# 04_Output_Display.net
KiCad netlist of a schematic drawn in Altium Designer
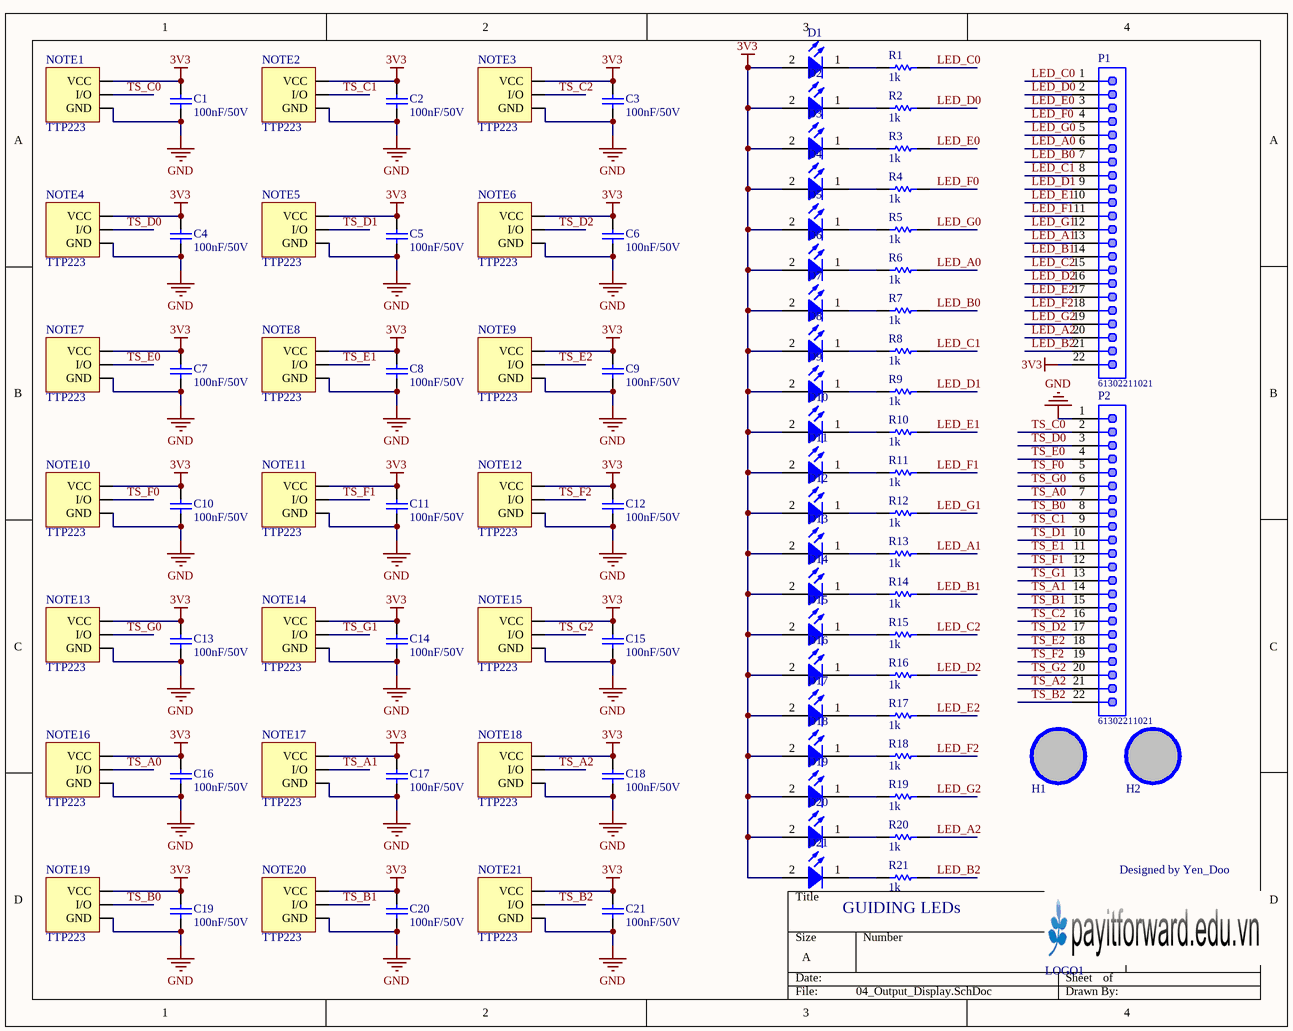
[diagram p0: 04_Output_Display.SchDoc]

(export (version "E")
  (design (tool "Eeschema 10.0.6"))
  (components
    (comp (ref "*1")
      (value "LOGO_DOO")
      (footprint "Logo_Top_Overlay")
      (libsource (lib "YenDoo") (part "LOGO_DOO"))
    )
    (comp (ref "C1")
      (value "100nF/50V")
      (footprint "CAP-SM-0805")
      (description "CAP CER 0.1UF 50V Y5V 0805")
      (fields
        (field (name "MANUFACTURER") "Samsung Electro-Mechanics")
        (field (name "MANUFACTURER PART NUMBER") "CL21F104ZBCNNNC")
      )
      (libsource (lib "Capacitor") (part "Cap-100nF-50V-0805"))
    )
    (comp (ref "C2")
      (value "100nF/50V")
      (footprint "CAP-SM-0805")
      (description "CAP CER 0.1UF 50V Y5V 0805")
      (fields
        (field (name "MANUFACTURER") "Samsung Electro-Mechanics")
        (field (name "MANUFACTURER PART NUMBER") "CL21F104ZBCNNNC")
      )
      (libsource (lib "Capacitor") (part "Cap-100nF-50V-0805"))
    )
    (comp (ref "C3")
      (value "100nF/50V")
      (footprint "CAP-SM-0805")
      (description "CAP CER 0.1UF 50V Y5V 0805")
      (fields
        (field (name "MANUFACTURER") "Samsung Electro-Mechanics")
        (field (name "MANUFACTURER PART NUMBER") "CL21F104ZBCNNNC")
      )
      (libsource (lib "Capacitor") (part "Cap-100nF-50V-0805"))
    )
    (comp (ref "C4")
      (value "100nF/50V")
      (footprint "CAP-SM-0805")
      (description "CAP CER 0.1UF 50V Y5V 0805")
      (fields
        (field (name "MANUFACTURER") "Samsung Electro-Mechanics")
        (field (name "MANUFACTURER PART NUMBER") "CL21F104ZBCNNNC")
      )
      (libsource (lib "Capacitor") (part "Cap-100nF-50V-0805"))
    )
    (comp (ref "C5")
      (value "100nF/50V")
      (footprint "CAP-SM-0805")
      (description "CAP CER 0.1UF 50V Y5V 0805")
      (fields
        (field (name "MANUFACTURER") "Samsung Electro-Mechanics")
        (field (name "MANUFACTURER PART NUMBER") "CL21F104ZBCNNNC")
      )
      (libsource (lib "Capacitor") (part "Cap-100nF-50V-0805"))
    )
    (comp (ref "C6")
      (value "100nF/50V")
      (footprint "CAP-SM-0805")
      (description "CAP CER 0.1UF 50V Y5V 0805")
      (fields
        (field (name "MANUFACTURER") "Samsung Electro-Mechanics")
        (field (name "MANUFACTURER PART NUMBER") "CL21F104ZBCNNNC")
      )
      (libsource (lib "Capacitor") (part "Cap-100nF-50V-0805"))
    )
    (comp (ref "C7")
      (value "100nF/50V")
      (footprint "CAP-SM-0805")
      (description "CAP CER 0.1UF 50V Y5V 0805")
      (fields
        (field (name "MANUFACTURER") "Samsung Electro-Mechanics")
        (field (name "MANUFACTURER PART NUMBER") "CL21F104ZBCNNNC")
      )
      (libsource (lib "Capacitor") (part "Cap-100nF-50V-0805"))
    )
    (comp (ref "C8")
      (value "100nF/50V")
      (footprint "CAP-SM-0805")
      (description "CAP CER 0.1UF 50V Y5V 0805")
      (fields
        (field (name "MANUFACTURER") "Samsung Electro-Mechanics")
        (field (name "MANUFACTURER PART NUMBER") "CL21F104ZBCNNNC")
      )
      (libsource (lib "Capacitor") (part "Cap-100nF-50V-0805"))
    )
    (comp (ref "C9")
      (value "100nF/50V")
      (footprint "CAP-SM-0805")
      (description "CAP CER 0.1UF 50V Y5V 0805")
      (fields
        (field (name "MANUFACTURER") "Samsung Electro-Mechanics")
        (field (name "MANUFACTURER PART NUMBER") "CL21F104ZBCNNNC")
      )
      (libsource (lib "Capacitor") (part "Cap-100nF-50V-0805"))
    )
    (comp (ref "C10")
      (value "100nF/50V")
      (footprint "CAP-SM-0805")
      (description "CAP CER 0.1UF 50V Y5V 0805")
      (fields
        (field (name "MANUFACTURER") "Samsung Electro-Mechanics")
        (field (name "MANUFACTURER PART NUMBER") "CL21F104ZBCNNNC")
      )
      (libsource (lib "Capacitor") (part "Cap-100nF-50V-0805"))
    )
    (comp (ref "C11")
      (value "100nF/50V")
      (footprint "CAP-SM-0805")
      (description "CAP CER 0.1UF 50V Y5V 0805")
      (fields
        (field (name "MANUFACTURER") "Samsung Electro-Mechanics")
        (field (name "MANUFACTURER PART NUMBER") "CL21F104ZBCNNNC")
      )
      (libsource (lib "Capacitor") (part "Cap-100nF-50V-0805"))
    )
    (comp (ref "C12")
      (value "100nF/50V")
      (footprint "CAP-SM-0805")
      (description "CAP CER 0.1UF 50V Y5V 0805")
      (fields
        (field (name "MANUFACTURER") "Samsung Electro-Mechanics")
        (field (name "MANUFACTURER PART NUMBER") "CL21F104ZBCNNNC")
      )
      (libsource (lib "Capacitor") (part "Cap-100nF-50V-0805"))
    )
    (comp (ref "C13")
      (value "100nF/50V")
      (footprint "CAP-SM-0805")
      (description "CAP CER 0.1UF 50V Y5V 0805")
      (fields
        (field (name "MANUFACTURER") "Samsung Electro-Mechanics")
        (field (name "MANUFACTURER PART NUMBER") "CL21F104ZBCNNNC")
      )
      (libsource (lib "Capacitor") (part "Cap-100nF-50V-0805"))
    )
    (comp (ref "C14")
      (value "100nF/50V")
      (footprint "CAP-SM-0805")
      (description "CAP CER 0.1UF 50V Y5V 0805")
      (fields
        (field (name "MANUFACTURER") "Samsung Electro-Mechanics")
        (field (name "MANUFACTURER PART NUMBER") "CL21F104ZBCNNNC")
      )
      (libsource (lib "Capacitor") (part "Cap-100nF-50V-0805"))
    )
    (comp (ref "C15")
      (value "100nF/50V")
      (footprint "CAP-SM-0805")
      (description "CAP CER 0.1UF 50V Y5V 0805")
      (fields
        (field (name "MANUFACTURER") "Samsung Electro-Mechanics")
        (field (name "MANUFACTURER PART NUMBER") "CL21F104ZBCNNNC")
      )
      (libsource (lib "Capacitor") (part "Cap-100nF-50V-0805"))
    )
    (comp (ref "C16")
      (value "100nF/50V")
      (footprint "CAP-SM-0805")
      (description "CAP CER 0.1UF 50V Y5V 0805")
      (fields
        (field (name "MANUFACTURER") "Samsung Electro-Mechanics")
        (field (name "MANUFACTURER PART NUMBER") "CL21F104ZBCNNNC")
      )
      (libsource (lib "Capacitor") (part "Cap-100nF-50V-0805"))
    )
    (comp (ref "C17")
      (value "100nF/50V")
      (footprint "CAP-SM-0805")
      (description "CAP CER 0.1UF 50V Y5V 0805")
      (fields
        (field (name "MANUFACTURER") "Samsung Electro-Mechanics")
        (field (name "MANUFACTURER PART NUMBER") "CL21F104ZBCNNNC")
      )
      (libsource (lib "Capacitor") (part "Cap-100nF-50V-0805"))
    )
    (comp (ref "C18")
      (value "100nF/50V")
      (footprint "CAP-SM-0805")
      (description "CAP CER 0.1UF 50V Y5V 0805")
      (fields
        (field (name "MANUFACTURER") "Samsung Electro-Mechanics")
        (field (name "MANUFACTURER PART NUMBER") "CL21F104ZBCNNNC")
      )
      (libsource (lib "Capacitor") (part "Cap-100nF-50V-0805"))
    )
    (comp (ref "C19")
      (value "100nF/50V")
      (footprint "CAP-SM-0805")
      (description "CAP CER 0.1UF 50V Y5V 0805")
      (fields
        (field (name "MANUFACTURER") "Samsung Electro-Mechanics")
        (field (name "MANUFACTURER PART NUMBER") "CL21F104ZBCNNNC")
      )
      (libsource (lib "Capacitor") (part "Cap-100nF-50V-0805"))
    )
    (comp (ref "C20")
      (value "100nF/50V")
      (footprint "CAP-SM-0805")
      (description "CAP CER 0.1UF 50V Y5V 0805")
      (fields
        (field (name "MANUFACTURER") "Samsung Electro-Mechanics")
        (field (name "MANUFACTURER PART NUMBER") "CL21F104ZBCNNNC")
      )
      (libsource (lib "Capacitor") (part "Cap-100nF-50V-0805"))
    )
    (comp (ref "C21")
      (value "100nF/50V")
      (footprint "CAP-SM-0805")
      (description "CAP CER 0.1UF 50V Y5V 0805")
      (fields
        (field (name "MANUFACTURER") "Samsung Electro-Mechanics")
        (field (name "MANUFACTURER PART NUMBER") "CL21F104ZBCNNNC")
      )
      (libsource (lib "Capacitor") (part "Cap-100nF-50V-0805"))
    )
    (comp (ref "D1")
      (value "Blue, 3.2V")
      (footprint "WL-SMCW_0805")
      (description "WL-SMCW SMT Mono-color Chip LED Waterclear, size 0805, Blue, 3.2V, 140deg")
      (fields (field (name "PART NUMBER") "150080BS75000") (field (name "PUBLISHER") "Wurth Elektronik"))
      (libsource (lib "Altium_WL-SMCW (rev20a)") (part "150080BS75000"))
    )
    (comp (ref "D2")
      (value "Blue, 3.2V")
      (footprint "WL-SMCW_0805")
      (description "WL-SMCW SMT Mono-color Chip LED Waterclear, size 0805, Blue, 3.2V, 140deg")
      (fields (field (name "PART NUMBER") "150080BS75000") (field (name "PUBLISHER") "Wurth Elektronik"))
      (libsource (lib "Altium_WL-SMCW (rev20a)") (part "150080BS75000"))
    )
    (comp (ref "D3")
      (value "Blue, 3.2V")
      (footprint "WL-SMCW_0805")
      (description "WL-SMCW SMT Mono-color Chip LED Waterclear, size 0805, Blue, 3.2V, 140deg")
      (fields (field (name "PART NUMBER") "150080BS75000") (field (name "PUBLISHER") "Wurth Elektronik"))
      (libsource (lib "Altium_WL-SMCW (rev20a)") (part "150080BS75000"))
    )
    (comp (ref "D4")
      (value "Blue, 3.2V")
      (footprint "WL-SMCW_0805")
      (description "WL-SMCW SMT Mono-color Chip LED Waterclear, size 0805, Blue, 3.2V, 140deg")
      (fields (field (name "PART NUMBER") "150080BS75000") (field (name "PUBLISHER") "Wurth Elektronik"))
      (libsource (lib "Altium_WL-SMCW (rev20a)") (part "150080BS75000"))
    )
    (comp (ref "D5")
      (value "Blue, 3.2V")
      (footprint "WL-SMCW_0805")
      (description "WL-SMCW SMT Mono-color Chip LED Waterclear, size 0805, Blue, 3.2V, 140deg")
      (fields (field (name "PART NUMBER") "150080BS75000") (field (name "PUBLISHER") "Wurth Elektronik"))
      (libsource (lib "Altium_WL-SMCW (rev20a)") (part "150080BS75000"))
    )
    (comp (ref "D6")
      (value "Blue, 3.2V")
      (footprint "WL-SMCW_0805")
      (description "WL-SMCW SMT Mono-color Chip LED Waterclear, size 0805, Blue, 3.2V, 140deg")
      (fields (field (name "PART NUMBER") "150080BS75000") (field (name "PUBLISHER") "Wurth Elektronik"))
      (libsource (lib "Altium_WL-SMCW (rev20a)") (part "150080BS75000"))
    )
    (comp (ref "D7")
      (value "Blue, 3.2V")
      (footprint "WL-SMCW_0805")
      (description "WL-SMCW SMT Mono-color Chip LED Waterclear, size 0805, Blue, 3.2V, 140deg")
      (fields (field (name "PART NUMBER") "150080BS75000") (field (name "PUBLISHER") "Wurth Elektronik"))
      (libsource (lib "Altium_WL-SMCW (rev20a)") (part "150080BS75000"))
    )
    (comp (ref "D8")
      (value "Blue, 3.2V")
      (footprint "WL-SMCW_0805")
      (description "WL-SMCW SMT Mono-color Chip LED Waterclear, size 0805, Blue, 3.2V, 140deg")
      (fields (field (name "PART NUMBER") "150080BS75000") (field (name "PUBLISHER") "Wurth Elektronik"))
      (libsource (lib "Altium_WL-SMCW (rev20a)") (part "150080BS75000"))
    )
    (comp (ref "D9")
      (value "Blue, 3.2V")
      (footprint "WL-SMCW_0805")
      (description "WL-SMCW SMT Mono-color Chip LED Waterclear, size 0805, Blue, 3.2V, 140deg")
      (fields (field (name "PART NUMBER") "150080BS75000") (field (name "PUBLISHER") "Wurth Elektronik"))
      (libsource (lib "Altium_WL-SMCW (rev20a)") (part "150080BS75000"))
    )
    (comp (ref "D10")
      (value "Blue, 3.2V")
      (footprint "WL-SMCW_0805")
      (description "WL-SMCW SMT Mono-color Chip LED Waterclear, size 0805, Blue, 3.2V, 140deg")
      (fields (field (name "PART NUMBER") "150080BS75000") (field (name "PUBLISHER") "Wurth Elektronik"))
      (libsource (lib "Altium_WL-SMCW (rev20a)") (part "150080BS75000"))
    )
    (comp (ref "D11")
      (value "Blue, 3.2V")
      (footprint "WL-SMCW_0805")
      (description "WL-SMCW SMT Mono-color Chip LED Waterclear, size 0805, Blue, 3.2V, 140deg")
      (fields (field (name "PART NUMBER") "150080BS75000") (field (name "PUBLISHER") "Wurth Elektronik"))
      (libsource (lib "Altium_WL-SMCW (rev20a)") (part "150080BS75000"))
    )
    (comp (ref "D12")
      (value "Blue, 3.2V")
      (footprint "WL-SMCW_0805")
      (description "WL-SMCW SMT Mono-color Chip LED Waterclear, size 0805, Blue, 3.2V, 140deg")
      (fields (field (name "PART NUMBER") "150080BS75000") (field (name "PUBLISHER") "Wurth Elektronik"))
      (libsource (lib "Altium_WL-SMCW (rev20a)") (part "150080BS75000"))
    )
    (comp (ref "D13")
      (value "Blue, 3.2V")
      (footprint "WL-SMCW_0805")
      (description "WL-SMCW SMT Mono-color Chip LED Waterclear, size 0805, Blue, 3.2V, 140deg")
      (fields (field (name "PART NUMBER") "150080BS75000") (field (name "PUBLISHER") "Wurth Elektronik"))
      (libsource (lib "Altium_WL-SMCW (rev20a)") (part "150080BS75000"))
    )
    (comp (ref "D14")
      (value "Blue, 3.2V")
      (footprint "WL-SMCW_0805")
      (description "WL-SMCW SMT Mono-color Chip LED Waterclear, size 0805, Blue, 3.2V, 140deg")
      (fields (field (name "PART NUMBER") "150080BS75000") (field (name "PUBLISHER") "Wurth Elektronik"))
      (libsource (lib "Altium_WL-SMCW (rev20a)") (part "150080BS75000"))
    )
    (comp (ref "D15")
      (value "Blue, 3.2V")
      (footprint "WL-SMCW_0805")
      (description "WL-SMCW SMT Mono-color Chip LED Waterclear, size 0805, Blue, 3.2V, 140deg")
      (fields (field (name "PART NUMBER") "150080BS75000") (field (name "PUBLISHER") "Wurth Elektronik"))
      (libsource (lib "Altium_WL-SMCW (rev20a)") (part "150080BS75000"))
    )
    (comp (ref "D16")
      (value "Blue, 3.2V")
      (footprint "WL-SMCW_0805")
      (description "WL-SMCW SMT Mono-color Chip LED Waterclear, size 0805, Blue, 3.2V, 140deg")
      (fields (field (name "PART NUMBER") "150080BS75000") (field (name "PUBLISHER") "Wurth Elektronik"))
      (libsource (lib "Altium_WL-SMCW (rev20a)") (part "150080BS75000"))
    )
    (comp (ref "D17")
      (value "Blue, 3.2V")
      (footprint "WL-SMCW_0805")
      (description "WL-SMCW SMT Mono-color Chip LED Waterclear, size 0805, Blue, 3.2V, 140deg")
      (fields (field (name "PART NUMBER") "150080BS75000") (field (name "PUBLISHER") "Wurth Elektronik"))
      (libsource (lib "Altium_WL-SMCW (rev20a)") (part "150080BS75000"))
    )
    (comp (ref "D18")
      (value "Blue, 3.2V")
      (footprint "WL-SMCW_0805")
      (description "WL-SMCW SMT Mono-color Chip LED Waterclear, size 0805, Blue, 3.2V, 140deg")
      (fields (field (name "PART NUMBER") "150080BS75000") (field (name "PUBLISHER") "Wurth Elektronik"))
      (libsource (lib "Altium_WL-SMCW (rev20a)") (part "150080BS75000"))
    )
    (comp (ref "D19")
      (value "Blue, 3.2V")
      (footprint "WL-SMCW_0805")
      (description "WL-SMCW SMT Mono-color Chip LED Waterclear, size 0805, Blue, 3.2V, 140deg")
      (fields (field (name "PART NUMBER") "150080BS75000") (field (name "PUBLISHER") "Wurth Elektronik"))
      (libsource (lib "Altium_WL-SMCW (rev20a)") (part "150080BS75000"))
    )
    (comp (ref "D20")
      (value "Blue, 3.2V")
      (footprint "WL-SMCW_0805")
      (description "WL-SMCW SMT Mono-color Chip LED Waterclear, size 0805, Blue, 3.2V, 140deg")
      (fields (field (name "PART NUMBER") "150080BS75000") (field (name "PUBLISHER") "Wurth Elektronik"))
      (libsource (lib "Altium_WL-SMCW (rev20a)") (part "150080BS75000"))
    )
    (comp (ref "D21")
      (value "Blue, 3.2V")
      (footprint "WL-SMCW_0805")
      (description "WL-SMCW SMT Mono-color Chip LED Waterclear, size 0805, Blue, 3.2V, 140deg")
      (fields (field (name "PART NUMBER") "150080BS75000") (field (name "PUBLISHER") "Wurth Elektronik"))
      (libsource (lib "Altium_WL-SMCW (rev20a)") (part "150080BS75000"))
    )
    (comp (ref "H1")
      (value "Hole")
      (footprint "LO KHOAN 3MM")
      (description "Hole 3mm")
      (libsource (lib "PIF_Library") (part "Hole"))
    )
    (comp (ref "H2")
      (value "Hole")
      (footprint "LO KHOAN 3MM")
      (description "Hole 3mm")
      (libsource (lib "PIF_Library") (part "Hole"))
    )
    (comp (ref "LOGO1")
      (value "LOGO PIF")
      (footprint "PIF LOGO BIG SSTOP")
      (libsource (lib "PIF_Library") (part "LOGO PIF"))
    )
    (comp (ref "NOTE1") (value "TTP223") (footprint "TTP223") (libsource (lib "YenDoo") (part "TTP223")))
    (comp (ref "NOTE2") (value "TTP223") (footprint "TTP223") (libsource (lib "YenDoo") (part "TTP223")))
    (comp (ref "NOTE3") (value "TTP223") (footprint "TTP223") (libsource (lib "YenDoo") (part "TTP223")))
    (comp (ref "NOTE4") (value "TTP223") (footprint "TTP223") (libsource (lib "YenDoo") (part "TTP223")))
    (comp (ref "NOTE5") (value "TTP223") (footprint "TTP223") (libsource (lib "YenDoo") (part "TTP223")))
    (comp (ref "NOTE6") (value "TTP223") (footprint "TTP223") (libsource (lib "YenDoo") (part "TTP223")))
    (comp (ref "NOTE7") (value "TTP223") (footprint "TTP223") (libsource (lib "YenDoo") (part "TTP223")))
    (comp (ref "NOTE8") (value "TTP223") (footprint "TTP223") (libsource (lib "YenDoo") (part "TTP223")))
    (comp (ref "NOTE9") (value "TTP223") (footprint "TTP223") (libsource (lib "YenDoo") (part "TTP223")))
    (comp (ref "NOTE10") (value "TTP223") (footprint "TTP223") (libsource (lib "YenDoo") (part "TTP223")))
    (comp (ref "NOTE11") (value "TTP223") (footprint "TTP223") (libsource (lib "YenDoo") (part "TTP223")))
    (comp (ref "NOTE12") (value "TTP223") (footprint "TTP223") (libsource (lib "YenDoo") (part "TTP223")))
    (comp (ref "NOTE13") (value "TTP223") (footprint "TTP223") (libsource (lib "YenDoo") (part "TTP223")))
    (comp (ref "NOTE14") (value "TTP223") (footprint "TTP223") (libsource (lib "YenDoo") (part "TTP223")))
    (comp (ref "NOTE15") (value "TTP223") (footprint "TTP223") (libsource (lib "YenDoo") (part "TTP223")))
    (comp (ref "NOTE16") (value "TTP223") (footprint "TTP223") (libsource (lib "YenDoo") (part "TTP223")))
    (comp (ref "NOTE17") (value "TTP223") (footprint "TTP223") (libsource (lib "YenDoo") (part "TTP223")))
    (comp (ref "NOTE18") (value "TTP223") (footprint "TTP223") (libsource (lib "YenDoo") (part "TTP223")))
    (comp (ref "NOTE19") (value "TTP223") (footprint "TTP223") (libsource (lib "YenDoo") (part "TTP223")))
    (comp (ref "NOTE20") (value "TTP223") (footprint "TTP223") (libsource (lib "YenDoo") (part "TTP223")))
    (comp (ref "NOTE21") (value "TTP223") (footprint "TTP223") (libsource (lib "YenDoo") (part "TTP223")))
    (comp (ref "P1")
      (value "61302211021")
      (footprint "61302211021")
      (description "WR-PHD Pin Header, THT, pitch 2.54mm, Single Row, Angled, 22p")
      (fields (field (name "MANUFACTURER") "Wurth Elektronik"))
      (libsource (lib "Altium_WR-PHD (rev20a)") (part "61302211021"))
    )
    (comp (ref "P2")
      (value "61302211021")
      (footprint "61302211021")
      (description "WR-PHD Pin Header, THT, pitch 2.54mm, Single Row, Angled, 22p")
      (fields (field (name "MANUFACTURER") "Wurth Elektronik"))
      (libsource (lib "Altium_WR-PHD (rev20a)") (part "61302211021"))
    )
    (comp (ref "R1")
      (value "1k")
      (footprint "RES-SM-0805")
      (description "Resistor")
      (fields (field (name "Comment") "RESISTOR SMD"))
      (libsource (lib "PIF_Library") (part "RESISTOR SMD"))
    )
    (comp (ref "R2")
      (value "1k")
      (footprint "RES-SM-0805")
      (description "Resistor")
      (fields (field (name "Comment") "RESISTOR SMD"))
      (libsource (lib "PIF_Library") (part "RESISTOR SMD"))
    )
    (comp (ref "R3")
      (value "1k")
      (footprint "RES-SM-0805")
      (description "Resistor")
      (fields (field (name "Comment") "RESISTOR SMD"))
      (libsource (lib "PIF_Library") (part "RESISTOR SMD"))
    )
    (comp (ref "R4")
      (value "1k")
      (footprint "RES-SM-0805")
      (description "Resistor")
      (fields (field (name "Comment") "RESISTOR SMD"))
      (libsource (lib "PIF_Library") (part "RESISTOR SMD"))
    )
    (comp (ref "R5")
      (value "1k")
      (footprint "RES-SM-0805")
      (description "Resistor")
      (fields (field (name "Comment") "RESISTOR SMD"))
      (libsource (lib "PIF_Library") (part "RESISTOR SMD"))
    )
    (comp (ref "R6")
      (value "1k")
      (footprint "RES-SM-0805")
      (description "Resistor")
      (fields (field (name "Comment") "RESISTOR SMD"))
      (libsource (lib "PIF_Library") (part "RESISTOR SMD"))
    )
    (comp (ref "R7")
      (value "1k")
      (footprint "RES-SM-0805")
      (description "Resistor")
      (fields (field (name "Comment") "RESISTOR SMD"))
      (libsource (lib "PIF_Library") (part "RESISTOR SMD"))
    )
    (comp (ref "R8")
      (value "1k")
      (footprint "RES-SM-0805")
      (description "Resistor")
      (fields (field (name "Comment") "RESISTOR SMD"))
      (libsource (lib "PIF_Library") (part "RESISTOR SMD"))
    )
    (comp (ref "R9")
      (value "1k")
      (footprint "RES-SM-0805")
      (description "Resistor")
      (fields (field (name "Comment") "RESISTOR SMD"))
      (libsource (lib "PIF_Library") (part "RESISTOR SMD"))
    )
    (comp (ref "R10")
      (value "1k")
      (footprint "RES-SM-0805")
      (description "Resistor")
      (fields (field (name "Comment") "RESISTOR SMD"))
      (libsource (lib "PIF_Library") (part "RESISTOR SMD"))
    )
    (comp (ref "R11")
      (value "1k")
      (footprint "RES-SM-0805")
      (description "Resistor")
      (fields (field (name "Comment") "RESISTOR SMD"))
      (libsource (lib "PIF_Library") (part "RESISTOR SMD"))
    )
    (comp (ref "R12")
      (value "1k")
      (footprint "RES-SM-0805")
      (description "Resistor")
      (fields (field (name "Comment") "RESISTOR SMD"))
      (libsource (lib "PIF_Library") (part "RESISTOR SMD"))
    )
    (comp (ref "R13")
      (value "1k")
      (footprint "RES-SM-0805")
      (description "Resistor")
      (fields (field (name "Comment") "RESISTOR SMD"))
      (libsource (lib "PIF_Library") (part "RESISTOR SMD"))
    )
    (comp (ref "R14")
      (value "1k")
      (footprint "RES-SM-0805")
      (description "Resistor")
      (fields (field (name "Comment") "RESISTOR SMD"))
      (libsource (lib "PIF_Library") (part "RESISTOR SMD"))
    )
    (comp (ref "R15")
      (value "1k")
      (footprint "RES-SM-0805")
      (description "Resistor")
      (fields (field (name "Comment") "RESISTOR SMD"))
      (libsource (lib "PIF_Library") (part "RESISTOR SMD"))
    )
    (comp (ref "R16")
      (value "1k")
      (footprint "RES-SM-0805")
      (description "Resistor")
      (fields (field (name "Comment") "RESISTOR SMD"))
      (libsource (lib "PIF_Library") (part "RESISTOR SMD"))
    )
    (comp (ref "R17")
      (value "1k")
      (footprint "RES-SM-0805")
      (description "Resistor")
      (fields (field (name "Comment") "RESISTOR SMD"))
      (libsource (lib "PIF_Library") (part "RESISTOR SMD"))
    )
    (comp (ref "R18")
      (value "1k")
      (footprint "RES-SM-0805")
      (description "Resistor")
      (fields (field (name "Comment") "RESISTOR SMD"))
      (libsource (lib "PIF_Library") (part "RESISTOR SMD"))
    )
    (comp (ref "R19")
      (value "1k")
      (footprint "RES-SM-0805")
      (description "Resistor")
      (fields (field (name "Comment") "RESISTOR SMD"))
      (libsource (lib "PIF_Library") (part "RESISTOR SMD"))
    )
    (comp (ref "R20")
      (value "1k")
      (footprint "RES-SM-0805")
      (description "Resistor")
      (fields (field (name "Comment") "RESISTOR SMD"))
      (libsource (lib "PIF_Library") (part "RESISTOR SMD"))
    )
    (comp (ref "R21")
      (value "1k")
      (footprint "RES-SM-0805")
      (description "Resistor")
      (fields (field (name "Comment") "RESISTOR SMD"))
      (libsource (lib "PIF_Library") (part "RESISTOR SMD"))
    )
  )
  (nets
    (net (code "1") (name "/LED_A0") (class "Default")
      (node (ref "P1") (pin "6") (pinfunction "6_6") (pintype "passive"))
      (node (ref "R6") (pin "1") (pinfunction "1_1") (pintype "passive"))
    )
    (net (code "2") (name "/LED_A1") (class "Default")
      (node (ref "P1") (pin "13") (pinfunction "13_13") (pintype "passive"))
      (node (ref "R13") (pin "1") (pinfunction "1_1") (pintype "passive"))
    )
    (net (code "3") (name "/LED_A2") (class "Default")
      (node (ref "P1") (pin "20") (pinfunction "20_20") (pintype "passive"))
      (node (ref "R20") (pin "1") (pinfunction "1_1") (pintype "passive"))
    )
    (net (code "4") (name "/LED_B0") (class "Default")
      (node (ref "P1") (pin "7") (pinfunction "7_7") (pintype "passive"))
      (node (ref "R7") (pin "1") (pinfunction "1_1") (pintype "passive"))
    )
    (net (code "5") (name "/LED_B1") (class "Default")
      (node (ref "P1") (pin "14") (pinfunction "14_14") (pintype "passive"))
      (node (ref "R14") (pin "1") (pinfunction "1_1") (pintype "passive"))
    )
    (net (code "6") (name "/LED_B2") (class "Default")
      (node (ref "P1") (pin "21") (pinfunction "21_21") (pintype "passive"))
      (node (ref "R21") (pin "1") (pinfunction "1_1") (pintype "passive"))
    )
    (net (code "7") (name "/LED_C0") (class "Default")
      (node (ref "P1") (pin "1") (pinfunction "1_1") (pintype "passive"))
      (node (ref "R1") (pin "1") (pinfunction "1_1") (pintype "passive"))
    )
    (net (code "8") (name "/LED_C1") (class "Default")
      (node (ref "P1") (pin "8") (pinfunction "8_8") (pintype "passive"))
      (node (ref "R8") (pin "1") (pinfunction "1_1") (pintype "passive"))
    )
    (net (code "9") (name "/LED_C2") (class "Default")
      (node (ref "P1") (pin "15") (pinfunction "15_15") (pintype "passive"))
      (node (ref "R15") (pin "1") (pinfunction "1_1") (pintype "passive"))
    )
    (net (code "10") (name "/LED_D0") (class "Default")
      (node (ref "P1") (pin "2") (pinfunction "2_2") (pintype "passive"))
      (node (ref "R2") (pin "1") (pinfunction "1_1") (pintype "passive"))
    )
    (net (code "11") (name "/LED_D1") (class "Default")
      (node (ref "P1") (pin "9") (pinfunction "9_9") (pintype "passive"))
      (node (ref "R9") (pin "1") (pinfunction "1_1") (pintype "passive"))
    )
    (net (code "12") (name "/LED_D2") (class "Default")
      (node (ref "P1") (pin "16") (pinfunction "16_16") (pintype "passive"))
      (node (ref "R16") (pin "1") (pinfunction "1_1") (pintype "passive"))
    )
    (net (code "13") (name "/LED_E0") (class "Default")
      (node (ref "P1") (pin "3") (pinfunction "3_3") (pintype "passive"))
      (node (ref "R3") (pin "1") (pinfunction "1_1") (pintype "passive"))
    )
    (net (code "14") (name "/LED_E1") (class "Default")
      (node (ref "P1") (pin "10") (pinfunction "10_10") (pintype "passive"))
      (node (ref "R10") (pin "1") (pinfunction "1_1") (pintype "passive"))
    )
    (net (code "15") (name "/LED_E2") (class "Default")
      (node (ref "P1") (pin "17") (pinfunction "17_17") (pintype "passive"))
      (node (ref "R17") (pin "1") (pinfunction "1_1") (pintype "passive"))
    )
    (net (code "16") (name "/LED_F0") (class "Default")
      (node (ref "P1") (pin "4") (pinfunction "4_4") (pintype "passive"))
      (node (ref "R4") (pin "1") (pinfunction "1_1") (pintype "passive"))
    )
    (net (code "17") (name "/LED_F1") (class "Default")
      (node (ref "P1") (pin "11") (pinfunction "11_11") (pintype "passive"))
      (node (ref "R11") (pin "1") (pinfunction "1_1") (pintype "passive"))
    )
    (net (code "18") (name "/LED_F2") (class "Default")
      (node (ref "P1") (pin "18") (pinfunction "18_18") (pintype "passive"))
      (node (ref "R18") (pin "1") (pinfunction "1_1") (pintype "passive"))
    )
    (net (code "19") (name "/LED_G0") (class "Default")
      (node (ref "P1") (pin "5") (pinfunction "5_5") (pintype "passive"))
      (node (ref "R5") (pin "1") (pinfunction "1_1") (pintype "passive"))
    )
    (net (code "20") (name "/LED_G1") (class "Default")
      (node (ref "P1") (pin "12") (pinfunction "12_12") (pintype "passive"))
      (node (ref "R12") (pin "1") (pinfunction "1_1") (pintype "passive"))
    )
    (net (code "21") (name "/LED_G2") (class "Default")
      (node (ref "P1") (pin "19") (pinfunction "19_19") (pintype "passive"))
      (node (ref "R19") (pin "1") (pinfunction "1_1") (pintype "passive"))
    )
    (net (code "22") (name "/TS_A0") (class "Default")
      (node (ref "NOTE16") (pin "2") (pinfunction "I/O_2") (pintype "passive"))
      (node (ref "P2") (pin "7") (pinfunction "7_7") (pintype "passive"))
    )
    (net (code "23") (name "/TS_A1") (class "Default")
      (node (ref "NOTE17") (pin "2") (pinfunction "I/O_2") (pintype "passive"))
      (node (ref "P2") (pin "14") (pinfunction "14_14") (pintype "passive"))
    )
    (net (code "24") (name "/TS_A2") (class "Default")
      (node (ref "NOTE18") (pin "2") (pinfunction "I/O_2") (pintype "passive"))
      (node (ref "P2") (pin "21") (pinfunction "21_21") (pintype "passive"))
    )
    (net (code "25") (name "/TS_B0") (class "Default")
      (node (ref "NOTE19") (pin "2") (pinfunction "I/O_2") (pintype "passive"))
      (node (ref "P2") (pin "8") (pinfunction "8_8") (pintype "passive"))
    )
    (net (code "26") (name "/TS_B1") (class "Default")
      (node (ref "NOTE20") (pin "2") (pinfunction "I/O_2") (pintype "passive"))
      (node (ref "P2") (pin "15") (pinfunction "15_15") (pintype "passive"))
    )
    (net (code "27") (name "/TS_B2") (class "Default")
      (node (ref "NOTE21") (pin "2") (pinfunction "I/O_2") (pintype "passive"))
      (node (ref "P2") (pin "22") (pinfunction "22_22") (pintype "passive"))
    )
    (net (code "28") (name "/TS_C0") (class "Default")
      (node (ref "NOTE1") (pin "2") (pinfunction "I/O_2") (pintype "passive"))
      (node (ref "P2") (pin "2") (pinfunction "2_2") (pintype "passive"))
    )
    (net (code "29") (name "/TS_C1") (class "Default")
      (node (ref "NOTE2") (pin "2") (pinfunction "I/O_2") (pintype "passive"))
      (node (ref "P2") (pin "9") (pinfunction "9_9") (pintype "passive"))
    )
    (net (code "30") (name "/TS_C2") (class "Default")
      (node (ref "NOTE3") (pin "2") (pinfunction "I/O_2") (pintype "passive"))
      (node (ref "P2") (pin "16") (pinfunction "16_16") (pintype "passive"))
    )
    (net (code "31") (name "/TS_D0") (class "Default")
      (node (ref "NOTE4") (pin "2") (pinfunction "I/O_2") (pintype "passive"))
      (node (ref "P2") (pin "3") (pinfunction "3_3") (pintype "passive"))
    )
    (net (code "32") (name "/TS_D1") (class "Default")
      (node (ref "NOTE5") (pin "2") (pinfunction "I/O_2") (pintype "passive"))
      (node (ref "P2") (pin "10") (pinfunction "10_10") (pintype "passive"))
    )
    (net (code "33") (name "/TS_D2") (class "Default")
      (node (ref "NOTE6") (pin "2") (pinfunction "I/O_2") (pintype "passive"))
      (node (ref "P2") (pin "17") (pinfunction "17_17") (pintype "passive"))
    )
    (net (code "34") (name "/TS_E0") (class "Default")
      (node (ref "NOTE7") (pin "2") (pinfunction "I/O_2") (pintype "passive"))
      (node (ref "P2") (pin "4") (pinfunction "4_4") (pintype "passive"))
    )
    (net (code "35") (name "/TS_E1") (class "Default")
      (node (ref "NOTE8") (pin "2") (pinfunction "I/O_2") (pintype "passive"))
      (node (ref "P2") (pin "11") (pinfunction "11_11") (pintype "passive"))
    )
    (net (code "36") (name "/TS_E2") (class "Default")
      (node (ref "NOTE9") (pin "2") (pinfunction "I/O_2") (pintype "passive"))
      (node (ref "P2") (pin "18") (pinfunction "18_18") (pintype "passive"))
    )
    (net (code "37") (name "/TS_F0") (class "Default")
      (node (ref "NOTE10") (pin "2") (pinfunction "I/O_2") (pintype "passive"))
      (node (ref "P2") (pin "5") (pinfunction "5_5") (pintype "passive"))
    )
    (net (code "38") (name "/TS_F1") (class "Default")
      (node (ref "NOTE11") (pin "2") (pinfunction "I/O_2") (pintype "passive"))
      (node (ref "P2") (pin "12") (pinfunction "12_12") (pintype "passive"))
    )
    (net (code "39") (name "/TS_F2") (class "Default")
      (node (ref "NOTE12") (pin "2") (pinfunction "I/O_2") (pintype "passive"))
      (node (ref "P2") (pin "19") (pinfunction "19_19") (pintype "passive"))
    )
    (net (code "40") (name "/TS_G0") (class "Default")
      (node (ref "NOTE13") (pin "2") (pinfunction "I/O_2") (pintype "passive"))
      (node (ref "P2") (pin "6") (pinfunction "6_6") (pintype "passive"))
    )
    (net (code "41") (name "/TS_G1") (class "Default")
      (node (ref "NOTE14") (pin "2") (pinfunction "I/O_2") (pintype "passive"))
      (node (ref "P2") (pin "13") (pinfunction "13_13") (pintype "passive"))
    )
    (net (code "42") (name "/TS_G2") (class "Default")
      (node (ref "NOTE15") (pin "2") (pinfunction "I/O_2") (pintype "passive"))
      (node (ref "P2") (pin "20") (pinfunction "20_20") (pintype "passive"))
    )
    (net (code "43") (name "3V3") (class "Default")
      (node (ref "C1") (pin "2") (pinfunction "2_2") (pintype "passive"))
      (node (ref "C10") (pin "2") (pinfunction "2_2") (pintype "passive"))
      (node (ref "C11") (pin "2") (pinfunction "2_2") (pintype "passive"))
      (node (ref "C12") (pin "2") (pinfunction "2_2") (pintype "passive"))
      (node (ref "C13") (pin "2") (pinfunction "2_2") (pintype "passive"))
      (node (ref "C14") (pin "2") (pinfunction "2_2") (pintype "passive"))
      (node (ref "C15") (pin "2") (pinfunction "2_2") (pintype "passive"))
      (node (ref "C16") (pin "2") (pinfunction "2_2") (pintype "passive"))
      (node (ref "C17") (pin "2") (pinfunction "2_2") (pintype "passive"))
      (node (ref "C18") (pin "2") (pinfunction "2_2") (pintype "passive"))
      (node (ref "C19") (pin "2") (pinfunction "2_2") (pintype "passive"))
      (node (ref "C2") (pin "2") (pinfunction "2_2") (pintype "passive"))
      (node (ref "C20") (pin "2") (pinfunction "2_2") (pintype "passive"))
      (node (ref "C21") (pin "2") (pinfunction "2_2") (pintype "passive"))
      (node (ref "C3") (pin "2") (pinfunction "2_2") (pintype "passive"))
      (node (ref "C4") (pin "2") (pinfunction "2_2") (pintype "passive"))
      (node (ref "C5") (pin "2") (pinfunction "2_2") (pintype "passive"))
      (node (ref "C6") (pin "2") (pinfunction "2_2") (pintype "passive"))
      (node (ref "C7") (pin "2") (pinfunction "2_2") (pintype "passive"))
      (node (ref "C8") (pin "2") (pinfunction "2_2") (pintype "passive"))
      (node (ref "C9") (pin "2") (pinfunction "2_2") (pintype "passive"))
      (node (ref "D1") (pin "2") (pinfunction "A_2") (pintype "passive"))
      (node (ref "D10") (pin "2") (pinfunction "A_2") (pintype "passive"))
      (node (ref "D11") (pin "2") (pinfunction "A_2") (pintype "passive"))
      (node (ref "D12") (pin "2") (pinfunction "A_2") (pintype "passive"))
      (node (ref "D13") (pin "2") (pinfunction "A_2") (pintype "passive"))
      (node (ref "D14") (pin "2") (pinfunction "A_2") (pintype "passive"))
      (node (ref "D15") (pin "2") (pinfunction "A_2") (pintype "passive"))
      (node (ref "D16") (pin "2") (pinfunction "A_2") (pintype "passive"))
      (node (ref "D17") (pin "2") (pinfunction "A_2") (pintype "passive"))
      (node (ref "D18") (pin "2") (pinfunction "A_2") (pintype "passive"))
      (node (ref "D19") (pin "2") (pinfunction "A_2") (pintype "passive"))
      (node (ref "D2") (pin "2") (pinfunction "A_2") (pintype "passive"))
      (node (ref "D20") (pin "2") (pinfunction "A_2") (pintype "passive"))
      (node (ref "D21") (pin "2") (pinfunction "A_2") (pintype "passive"))
      (node (ref "D3") (pin "2") (pinfunction "A_2") (pintype "passive"))
      (node (ref "D4") (pin "2") (pinfunction "A_2") (pintype "passive"))
      (node (ref "D5") (pin "2") (pinfunction "A_2") (pintype "passive"))
      (node (ref "D6") (pin "2") (pinfunction "A_2") (pintype "passive"))
      (node (ref "D7") (pin "2") (pinfunction "A_2") (pintype "passive"))
      (node (ref "D8") (pin "2") (pinfunction "A_2") (pintype "passive"))
      (node (ref "D9") (pin "2") (pinfunction "A_2") (pintype "passive"))
      (node (ref "NOTE1") (pin "3") (pinfunction "VCC_3") (pintype "passive"))
      (node (ref "NOTE10") (pin "3") (pinfunction "VCC_3") (pintype "passive"))
      (node (ref "NOTE11") (pin "3") (pinfunction "VCC_3") (pintype "passive"))
      (node (ref "NOTE12") (pin "3") (pinfunction "VCC_3") (pintype "passive"))
      (node (ref "NOTE13") (pin "3") (pinfunction "VCC_3") (pintype "passive"))
      (node (ref "NOTE14") (pin "3") (pinfunction "VCC_3") (pintype "passive"))
      (node (ref "NOTE15") (pin "3") (pinfunction "VCC_3") (pintype "passive"))
      (node (ref "NOTE16") (pin "3") (pinfunction "VCC_3") (pintype "passive"))
      (node (ref "NOTE17") (pin "3") (pinfunction "VCC_3") (pintype "passive"))
      (node (ref "NOTE18") (pin "3") (pinfunction "VCC_3") (pintype "passive"))
      (node (ref "NOTE19") (pin "3") (pinfunction "VCC_3") (pintype "passive"))
      (node (ref "NOTE2") (pin "3") (pinfunction "VCC_3") (pintype "passive"))
      (node (ref "NOTE20") (pin "3") (pinfunction "VCC_3") (pintype "passive"))
      (node (ref "NOTE21") (pin "3") (pinfunction "VCC_3") (pintype "passive"))
      (node (ref "NOTE3") (pin "3") (pinfunction "VCC_3") (pintype "passive"))
      (node (ref "NOTE4") (pin "3") (pinfunction "VCC_3") (pintype "passive"))
      (node (ref "NOTE5") (pin "3") (pinfunction "VCC_3") (pintype "passive"))
      (node (ref "NOTE6") (pin "3") (pinfunction "VCC_3") (pintype "passive"))
      (node (ref "NOTE7") (pin "3") (pinfunction "VCC_3") (pintype "passive"))
      (node (ref "NOTE8") (pin "3") (pinfunction "VCC_3") (pintype "passive"))
      (node (ref "NOTE9") (pin "3") (pinfunction "VCC_3") (pintype "passive"))
      (node (ref "P1") (pin "22") (pinfunction "22_22") (pintype "passive"))
    )
    (net (code "44") (name "GND") (class "Default")
      (node (ref "C1") (pin "1") (pinfunction "1_1") (pintype "passive"))
      (node (ref "C10") (pin "1") (pinfunction "1_1") (pintype "passive"))
      (node (ref "C11") (pin "1") (pinfunction "1_1") (pintype "passive"))
      (node (ref "C12") (pin "1") (pinfunction "1_1") (pintype "passive"))
      (node (ref "C13") (pin "1") (pinfunction "1_1") (pintype "passive"))
      (node (ref "C14") (pin "1") (pinfunction "1_1") (pintype "passive"))
      (node (ref "C15") (pin "1") (pinfunction "1_1") (pintype "passive"))
      (node (ref "C16") (pin "1") (pinfunction "1_1") (pintype "passive"))
      (node (ref "C17") (pin "1") (pinfunction "1_1") (pintype "passive"))
      (node (ref "C18") (pin "1") (pinfunction "1_1") (pintype "passive"))
      (node (ref "C19") (pin "1") (pinfunction "1_1") (pintype "passive"))
      (node (ref "C2") (pin "1") (pinfunction "1_1") (pintype "passive"))
      (node (ref "C20") (pin "1") (pinfunction "1_1") (pintype "passive"))
      (node (ref "C21") (pin "1") (pinfunction "1_1") (pintype "passive"))
      (node (ref "C3") (pin "1") (pinfunction "1_1") (pintype "passive"))
      (node (ref "C4") (pin "1") (pinfunction "1_1") (pintype "passive"))
      (node (ref "C5") (pin "1") (pinfunction "1_1") (pintype "passive"))
      (node (ref "C6") (pin "1") (pinfunction "1_1") (pintype "passive"))
      (node (ref "C7") (pin "1") (pinfunction "1_1") (pintype "passive"))
      (node (ref "C8") (pin "1") (pinfunction "1_1") (pintype "passive"))
      (node (ref "C9") (pin "1") (pinfunction "1_1") (pintype "passive"))
      (node (ref "NOTE1") (pin "1") (pinfunction "GND_1") (pintype "passive"))
      (node (ref "NOTE10") (pin "1") (pinfunction "GND_1") (pintype "passive"))
      (node (ref "NOTE11") (pin "1") (pinfunction "GND_1") (pintype "passive"))
      (node (ref "NOTE12") (pin "1") (pinfunction "GND_1") (pintype "passive"))
      (node (ref "NOTE13") (pin "1") (pinfunction "GND_1") (pintype "passive"))
      (node (ref "NOTE14") (pin "1") (pinfunction "GND_1") (pintype "passive"))
      (node (ref "NOTE15") (pin "1") (pinfunction "GND_1") (pintype "passive"))
      (node (ref "NOTE16") (pin "1") (pinfunction "GND_1") (pintype "passive"))
      (node (ref "NOTE17") (pin "1") (pinfunction "GND_1") (pintype "passive"))
      (node (ref "NOTE18") (pin "1") (pinfunction "GND_1") (pintype "passive"))
      (node (ref "NOTE19") (pin "1") (pinfunction "GND_1") (pintype "passive"))
      (node (ref "NOTE2") (pin "1") (pinfunction "GND_1") (pintype "passive"))
      (node (ref "NOTE20") (pin "1") (pinfunction "GND_1") (pintype "passive"))
      (node (ref "NOTE21") (pin "1") (pinfunction "GND_1") (pintype "passive"))
      (node (ref "NOTE3") (pin "1") (pinfunction "GND_1") (pintype "passive"))
      (node (ref "NOTE4") (pin "1") (pinfunction "GND_1") (pintype "passive"))
      (node (ref "NOTE5") (pin "1") (pinfunction "GND_1") (pintype "passive"))
      (node (ref "NOTE6") (pin "1") (pinfunction "GND_1") (pintype "passive"))
      (node (ref "NOTE7") (pin "1") (pinfunction "GND_1") (pintype "passive"))
      (node (ref "NOTE8") (pin "1") (pinfunction "GND_1") (pintype "passive"))
      (node (ref "NOTE9") (pin "1") (pinfunction "GND_1") (pintype "passive"))
      (node (ref "P2") (pin "1") (pinfunction "1_1") (pintype "passive"))
    )
    (net (code "45") (name "Net-(D1-K)") (class "Default")
      (node (ref "D1") (pin "1") (pinfunction "K_1") (pintype "passive"))
      (node (ref "R1") (pin "2") (pinfunction "2_2") (pintype "passive"))
    )
    (net (code "46") (name "Net-(D2-K)") (class "Default")
      (node (ref "D2") (pin "1") (pinfunction "K_1") (pintype "passive"))
      (node (ref "R2") (pin "2") (pinfunction "2_2") (pintype "passive"))
    )
    (net (code "47") (name "Net-(D3-K)") (class "Default")
      (node (ref "D3") (pin "1") (pinfunction "K_1") (pintype "passive"))
      (node (ref "R3") (pin "2") (pinfunction "2_2") (pintype "passive"))
    )
    (net (code "48") (name "Net-(D4-K)") (class "Default")
      (node (ref "D4") (pin "1") (pinfunction "K_1") (pintype "passive"))
      (node (ref "R4") (pin "2") (pinfunction "2_2") (pintype "passive"))
    )
    (net (code "49") (name "Net-(D5-K)") (class "Default")
      (node (ref "D5") (pin "1") (pinfunction "K_1") (pintype "passive"))
      (node (ref "R5") (pin "2") (pinfunction "2_2") (pintype "passive"))
    )
    (net (code "50") (name "Net-(D6-K)") (class "Default")
      (node (ref "D6") (pin "1") (pinfunction "K_1") (pintype "passive"))
      (node (ref "R6") (pin "2") (pinfunction "2_2") (pintype "passive"))
    )
    (net (code "51") (name "Net-(D7-K)") (class "Default")
      (node (ref "D7") (pin "1") (pinfunction "K_1") (pintype "passive"))
      (node (ref "R7") (pin "2") (pinfunction "2_2") (pintype "passive"))
    )
    (net (code "52") (name "Net-(D8-K)") (class "Default")
      (node (ref "D8") (pin "1") (pinfunction "K_1") (pintype "passive"))
      (node (ref "R8") (pin "2") (pinfunction "2_2") (pintype "passive"))
    )
    (net (code "53") (name "Net-(D9-K)") (class "Default")
      (node (ref "D9") (pin "1") (pinfunction "K_1") (pintype "passive"))
      (node (ref "R9") (pin "2") (pinfunction "2_2") (pintype "passive"))
    )
    (net (code "54") (name "Net-(D10-K)") (class "Default")
      (node (ref "D10") (pin "1") (pinfunction "K_1") (pintype "passive"))
      (node (ref "R10") (pin "2") (pinfunction "2_2") (pintype "passive"))
    )
    (net (code "55") (name "Net-(D11-K)") (class "Default")
      (node (ref "D11") (pin "1") (pinfunction "K_1") (pintype "passive"))
      (node (ref "R11") (pin "2") (pinfunction "2_2") (pintype "passive"))
    )
    (net (code "56") (name "Net-(D12-K)") (class "Default")
      (node (ref "D12") (pin "1") (pinfunction "K_1") (pintype "passive"))
      (node (ref "R12") (pin "2") (pinfunction "2_2") (pintype "passive"))
    )
    (net (code "57") (name "Net-(D13-K)") (class "Default")
      (node (ref "D13") (pin "1") (pinfunction "K_1") (pintype "passive"))
      (node (ref "R13") (pin "2") (pinfunction "2_2") (pintype "passive"))
    )
    (net (code "58") (name "Net-(D14-K)") (class "Default")
      (node (ref "D14") (pin "1") (pinfunction "K_1") (pintype "passive"))
      (node (ref "R14") (pin "2") (pinfunction "2_2") (pintype "passive"))
    )
    (net (code "59") (name "Net-(D15-K)") (class "Default")
      (node (ref "D15") (pin "1") (pinfunction "K_1") (pintype "passive"))
      (node (ref "R15") (pin "2") (pinfunction "2_2") (pintype "passive"))
    )
    (net (code "60") (name "Net-(D16-K)") (class "Default")
      (node (ref "D16") (pin "1") (pinfunction "K_1") (pintype "passive"))
      (node (ref "R16") (pin "2") (pinfunction "2_2") (pintype "passive"))
    )
    (net (code "61") (name "Net-(D17-K)") (class "Default")
      (node (ref "D17") (pin "1") (pinfunction "K_1") (pintype "passive"))
      (node (ref "R17") (pin "2") (pinfunction "2_2") (pintype "passive"))
    )
    (net (code "62") (name "Net-(D18-K)") (class "Default")
      (node (ref "D18") (pin "1") (pinfunction "K_1") (pintype "passive"))
      (node (ref "R18") (pin "2") (pinfunction "2_2") (pintype "passive"))
    )
    (net (code "63") (name "Net-(D19-K)") (class "Default")
      (node (ref "D19") (pin "1") (pinfunction "K_1") (pintype "passive"))
      (node (ref "R19") (pin "2") (pinfunction "2_2") (pintype "passive"))
    )
    (net (code "64") (name "Net-(D20-K)") (class "Default")
      (node (ref "D20") (pin "1") (pinfunction "K_1") (pintype "passive"))
      (node (ref "R20") (pin "2") (pinfunction "2_2") (pintype "passive"))
    )
    (net (code "65") (name "Net-(D21-K)") (class "Default")
      (node (ref "D21") (pin "1") (pinfunction "K_1") (pintype "passive"))
      (node (ref "R21") (pin "2") (pinfunction "2_2") (pintype "passive"))
    )
    (net (code "66") (name "unconnected-(H1-Pad1)") (class "Default")
      (node (ref "H1") (pin "1") (pinfunction "1_1") (pintype "passive"))
    )
    (net (code "67") (name "unconnected-(H2-Pad1)") (class "Default")
      (node (ref "H2") (pin "1") (pinfunction "1_1") (pintype "passive"))
    )
  )
)
